# Motor_Module.net
KiCad netlist of a schematic drawn in Altium Designer
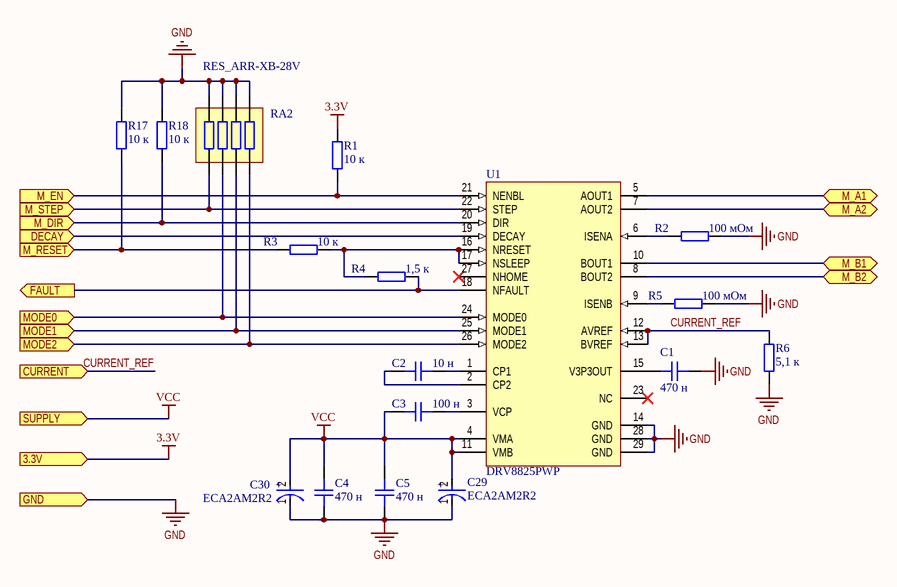
[diagram p0: Motor_Module.SchDoc]

(export (version "E")
  (design (tool "Eeschema 10.0.6"))
  (components
    (comp (ref "C1")
      (value "470 н")
      (footprint "CAP_0603")
      (description "Capacitor SMD 0805")
      (libsource (lib "Schematic-Lib-PhilsLab") (part "CAP_0805"))
    )
    (comp (ref "C2")
      (value "10 н")
      (footprint "CAP_0603")
      (description "Capacitor SMD 0805")
      (libsource (lib "Schematic-Lib-PhilsLab") (part "CAP_0805"))
    )
    (comp (ref "C3")
      (value "100 н")
      (footprint "CAP_0603")
      (description "Capacitor SMD 0805")
      (fields (field (name "VOLTAGE") "50"))
      (libsource (lib "Schematic-Lib-PhilsLab") (part "CAP_0805"))
    )
    (comp (ref "C4")
      (value "470 н")
      (footprint "CAP_0805")
      (description "Capacitor SMD 0805")
      (fields (field (name "VOLTAGE") "50"))
      (libsource (lib "Schematic-Lib-PhilsLab") (part "CAP_0805"))
    )
    (comp (ref "C5")
      (value "470 н")
      (footprint "CAP_0805")
      (description "Capacitor SMD 0805")
      (fields (field (name "VOLTAGE") "50"))
      (libsource (lib "Schematic-Lib-PhilsLab") (part "CAP_0805"))
    )
    (comp (ref "C29")
      (value "ECA2AM2R2")
      (footprint "FP-RAD-TH-D_5_0_5-L_11_1-MFG")
      (description "Aluminum Electrolytic Capacitors (Radial Lead Type) 2.2uF ±20% 100V")
      (fields (field (name "VOLTAGE") "16"))
      (libsource (lib "Altium Content Vault") (part "a00bbbee19879c290e62620ae7e47b1"))
    )
    (comp (ref "C30")
      (value "ECA2AM2R2")
      (footprint "FP-RAD-TH-D_5_0_5-L_11_1-MFG")
      (description "Aluminum Electrolytic Capacitors (Radial Lead Type) 2.2uF ±20% 100V")
      (fields (field (name "VOLTAGE") "16"))
      (libsource (lib "Altium Content Vault") (part "a00bbbee19879c290e62620ae7e47b1"))
    )
    (comp (ref "R1")
      (value "10 к")
      (footprint "RES_0603")
      (description "Resistor SMD 0805")
      (libsource (lib "Schematic-Lib-PhilsLab") (part "RES_0805"))
    )
    (comp (ref "R2")
      (value "100 мОм")
      (footprint "RES_1206")
      (description "Resistor SMD 1206")
      (libsource (lib "Schematic-Lib-PhilsLab") (part "RES_1206"))
    )
    (comp (ref "R3")
      (value "10 к")
      (footprint "RES_0603")
      (description "Resistor SMD 0805")
      (libsource (lib "Schematic-Lib-PhilsLab") (part "RES_0805"))
    )
    (comp (ref "R4")
      (value "1,5 к")
      (footprint "RES_0603")
      (description "Resistor SMD 0805")
      (libsource (lib "Schematic-Lib-PhilsLab") (part "RES_0805"))
    )
    (comp (ref "R5")
      (value "100 мОм")
      (footprint "RES_1206")
      (description "Resistor SMD 1206")
      (libsource (lib "Schematic-Lib-PhilsLab") (part "RES_1206"))
    )
    (comp (ref "R6")
      (value "5,1 к")
      (footprint "RES_0603")
      (description "Resistor SMD 0805")
      (libsource (lib "Schematic-Lib-PhilsLab") (part "RES_0805"))
    )
    (comp (ref "R17")
      (value "10 к")
      (footprint "RES_0603")
      (description "Resistor SMD 0805")
      (libsource (lib "Schematic-Lib-PhilsLab") (part "RES_0805"))
    )
    (comp (ref "R18")
      (value "10 к")
      (footprint "RES_0603")
      (description "Resistor SMD 0805")
      (libsource (lib "Schematic-Lib-PhilsLab") (part "RES_0805"))
    )
    (comp (ref "RA2")
      (value "RES_ARR-XB-28V")
      (footprint "EXB-28V")
      (description "Resistor Array 0402 4 Elements Panasonic EXB-28V")
      (libsource (lib "Schematic-Lib-PhilsLab") (part "RES_ARR-XB-28V"))
    )
    (comp (ref "U1")
      (value "DRV8825PWP")
      (footprint "PWP0028C_L")
      (libsource (lib "Altium Content Vault") (part "TI-DRV882XPWP28-XXXXXXXXXTP"))
    )
  )
  (nets
    (net (code "1") (name "/CURRENT_REF") (class "Default")
      (node (ref "R6") (pin "1") (pinfunction "1_1") (pintype "passive"))
      (node (ref "U1") (pin "12") (pinfunction "AVREF_12") (pintype "input"))
      (node (ref "U1") (pin "13") (pinfunction "BVREF_13") (pintype "input"))
    )
    (net (code "2") (name "/DECAY") (class "Default")
      (node (ref "U1") (pin "19") (pinfunction "DECAY_19") (pintype "input"))
    )
    (net (code "3") (name "/FAULT") (class "Default")
      (node (ref "R4") (pin "1") (pinfunction "1_1") (pintype "passive"))
      (node (ref "U1") (pin "18") (pinfunction "NFAULT_18") (pintype "open_collector"))
    )
    (net (code "4") (name "/MODE0") (class "Default")
      (node (ref "RA2") (pin "3") (pinfunction "3_3") (pintype "passive"))
      (node (ref "U1") (pin "24") (pinfunction "MODE0_24") (pintype "input"))
    )
    (net (code "5") (name "/MODE1") (class "Default")
      (node (ref "RA2") (pin "2") (pinfunction "2_2") (pintype "passive"))
      (node (ref "U1") (pin "25") (pinfunction "MODE1_25") (pintype "input"))
    )
    (net (code "6") (name "/MODE2") (class "Default")
      (node (ref "RA2") (pin "1") (pinfunction "1_1") (pintype "passive"))
      (node (ref "U1") (pin "26") (pinfunction "MODE2_26") (pintype "input"))
    )
    (net (code "7") (name "/M_A1") (class "Default")
      (node (ref "U1") (pin "5") (pinfunction "AOUT1_5") (pintype "tri_state"))
    )
    (net (code "8") (name "/M_A2") (class "Default")
      (node (ref "U1") (pin "7") (pinfunction "AOUT2_7") (pintype "tri_state"))
    )
    (net (code "9") (name "/M_B1") (class "Default")
      (node (ref "U1") (pin "10") (pinfunction "BOUT1_10") (pintype "tri_state"))
    )
    (net (code "10") (name "/M_B2") (class "Default")
      (node (ref "U1") (pin "8") (pinfunction "BOUT2_8") (pintype "tri_state"))
    )
    (net (code "11") (name "/M_DIR") (class "Default")
      (node (ref "R18") (pin "2") (pinfunction "2_2") (pintype "passive"))
      (node (ref "U1") (pin "20") (pinfunction "DIR_20") (pintype "input"))
    )
    (net (code "12") (name "/M_EN") (class "Default")
      (node (ref "R1") (pin "2") (pinfunction "2_2") (pintype "passive"))
      (node (ref "U1") (pin "21") (pinfunction "NENBL_21") (pintype "input"))
    )
    (net (code "13") (name "/M_RESET") (class "Default")
      (node (ref "R17") (pin "2") (pinfunction "2_2") (pintype "passive"))
      (node (ref "R3") (pin "2") (pinfunction "2_2") (pintype "passive"))
    )
    (net (code "14") (name "/M_STEP") (class "Default")
      (node (ref "RA2") (pin "4") (pinfunction "4_4") (pintype "passive"))
      (node (ref "U1") (pin "22") (pinfunction "STEP_22") (pintype "input"))
    )
    (net (code "15") (name "3.3V") (class "Default")
      (node (ref "R1") (pin "1") (pinfunction "1_1") (pintype "passive"))
    )
    (net (code "16") (name "GND") (class "Default")
      (node (ref "C1") (pin "2") (pinfunction "2_2") (pintype "passive"))
      (node (ref "C29") (pin "1") (pinfunction "C_1") (pintype "passive"))
      (node (ref "C30") (pin "1") (pinfunction "C_1") (pintype "passive"))
      (node (ref "C4") (pin "2") (pinfunction "2_2") (pintype "passive"))
      (node (ref "C5") (pin "2") (pinfunction "2_2") (pintype "passive"))
      (node (ref "R17") (pin "1") (pinfunction "1_1") (pintype "passive"))
      (node (ref "R18") (pin "1") (pinfunction "1_1") (pintype "passive"))
      (node (ref "R2") (pin "2") (pinfunction "2_2") (pintype "passive"))
      (node (ref "R5") (pin "2") (pinfunction "2_2") (pintype "passive"))
      (node (ref "R6") (pin "2") (pinfunction "2_2") (pintype "passive"))
      (node (ref "RA2") (pin "5") (pinfunction "5_5") (pintype "passive"))
      (node (ref "RA2") (pin "6") (pinfunction "6_6") (pintype "passive"))
      (node (ref "RA2") (pin "7") (pinfunction "7_7") (pintype "passive"))
      (node (ref "RA2") (pin "8") (pinfunction "8_8") (pintype "passive"))
      (node (ref "U1") (pin "14") (pinfunction "GND_14") (pintype "power_in"))
      (node (ref "U1") (pin "28") (pinfunction "GND_28") (pintype "power_in"))
      (node (ref "U1") (pin "29") (pinfunction "GND_29") (pintype "power_in"))
    )
    (net (code "17") (name "Net-(U1-CP1)") (class "Default")
      (node (ref "C2") (pin "1") (pinfunction "1_1") (pintype "passive"))
      (node (ref "U1") (pin "1") (pinfunction "CP1_1") (pintype "passive"))
    )
    (net (code "18") (name "Net-(U1-CP2)") (class "Default")
      (node (ref "C2") (pin "2") (pinfunction "2_2") (pintype "passive"))
      (node (ref "U1") (pin "2") (pinfunction "CP2_2") (pintype "passive"))
    )
    (net (code "19") (name "Net-(U1-ISENA)") (class "Default")
      (node (ref "R2") (pin "1") (pinfunction "1_1") (pintype "passive"))
      (node (ref "U1") (pin "6") (pinfunction "ISENA_6") (pintype "input"))
    )
    (net (code "20") (name "Net-(U1-ISENB)") (class "Default")
      (node (ref "R5") (pin "1") (pinfunction "1_1") (pintype "passive"))
      (node (ref "U1") (pin "9") (pinfunction "ISENB_9") (pintype "input"))
    )
    (net (code "21") (name "Net-(U1-NRESET)") (class "Default")
      (node (ref "R3") (pin "1") (pinfunction "1_1") (pintype "passive"))
      (node (ref "R4") (pin "2") (pinfunction "2_2") (pintype "passive"))
      (node (ref "U1") (pin "16") (pinfunction "NRESET_16") (pintype "input"))
      (node (ref "U1") (pin "17") (pinfunction "NSLEEP_17") (pintype "input"))
    )
    (net (code "22") (name "Net-(U1-V3P3OUT)") (class "Default")
      (node (ref "C1") (pin "1") (pinfunction "1_1") (pintype "passive"))
      (node (ref "U1") (pin "15") (pinfunction "V3P3OUT_15") (pintype "power_in"))
    )
    (net (code "23") (name "Net-(U1-VCP)") (class "Default")
      (node (ref "C3") (pin "2") (pinfunction "2_2") (pintype "passive"))
      (node (ref "U1") (pin "3") (pinfunction "VCP_3") (pintype "passive"))
    )
    (net (code "24") (name "VCC") (class "Default")
      (node (ref "C29") (pin "2") (pinfunction "A_2") (pintype "passive"))
      (node (ref "C3") (pin "1") (pinfunction "1_1") (pintype "passive"))
      (node (ref "C30") (pin "2") (pinfunction "A_2") (pintype "passive"))
      (node (ref "C4") (pin "1") (pinfunction "1_1") (pintype "passive"))
      (node (ref "C5") (pin "1") (pinfunction "1_1") (pintype "passive"))
      (node (ref "U1") (pin "11") (pinfunction "VMB_11") (pintype "power_in"))
      (node (ref "U1") (pin "4") (pinfunction "VMA_4") (pintype "power_in"))
    )
    (net (code "25") (name "unconnected-(U1-NC-Pad23)") (class "Default")
      (node (ref "U1") (pin "23") (pinfunction "NC_23") (pintype "passive+no_connect"))
    )
    (net (code "26") (name "unconnected-(U1-NHOME-Pad27)") (class "Default")
      (node (ref "U1") (pin "27") (pinfunction "NHOME_27") (pintype "open_collector+no_connect"))
    )
  )
)
